# BPDC_mid.net
KiCad netlist of a schematic drawn in Altium Designer
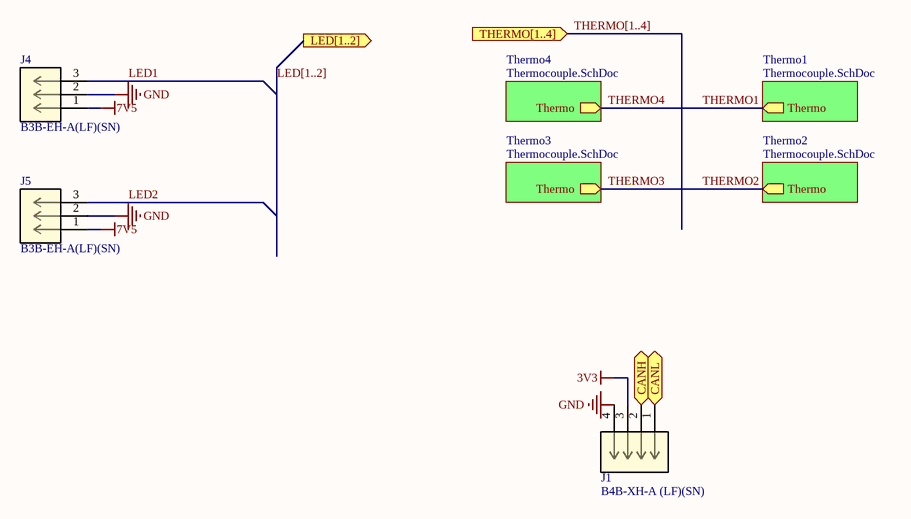
[diagram p0: BPDC mid.SchDoc]

(export (version "E")
  (design (tool "Eeschema 10.0.6"))
  (components
    (comp (ref "J1")
      (value "B4B-XH-A (LF)(SN)")
      (footprint "CONN_B4B-XH-A (LF)(SN)_JST")
      (description "No Description Available")
      (fields (field (name "COPYRIGHT") "Copyright (C) 2018 Accelerated Designs. All rights reserved"))
      (libsource (lib "BPDC conn") (part "B4B-XH-A (LF)(SN)"))
    )
    (comp (ref "J4")
      (value "B3B-EH-A(LF)(SN)")
      (footprint "CONN3_B3B-EH-A(LF)(SN)_JST")
      (description "No Description Available")
      (fields (field (name "COPYRIGHT") "Copyright (C) 2018 Accelerated Designs. All rights reserved"))
      (libsource (lib "photodiodeconn") (part "B3B-EH-A(LF)(SN)"))
    )
    (comp (ref "J5")
      (value "B3B-EH-A(LF)(SN)")
      (footprint "CONN3_B3B-EH-A(LF)(SN)_JST")
      (description "No Description Available")
      (fields (field (name "COPYRIGHT") "Copyright (C) 2018 Accelerated Designs. All rights reserved"))
      (libsource (lib "photodiodeconn") (part "B3B-EH-A(LF)(SN)"))
    )
  )
  (nets
    (net (code "1") (name "/CANH") (class "Default")
      (node (ref "J1") (pin "2") (pinfunction "2_2") (pintype "passive"))
    )
    (net (code "2") (name "/CANL") (class "Default")
      (node (ref "J1") (pin "1") (pinfunction "1_1") (pintype "passive"))
    )
    (net (code "3") (name "/LED1") (class "Default")
      (node (ref "J4") (pin "3") (pinfunction "3_3") (pintype "passive"))
    )
    (net (code "4") (name "/LED2") (class "Default")
      (node (ref "J5") (pin "3") (pinfunction "3_3") (pintype "passive"))
    )
    (net (code "9") (name "3V3") (class "Default")
      (node (ref "J1") (pin "3") (pinfunction "3_3") (pintype "passive"))
    )
    (net (code "10") (name "7V5") (class "Default")
      (node (ref "J4") (pin "1") (pinfunction "1_1") (pintype "passive"))
      (node (ref "J5") (pin "1") (pinfunction "1_1") (pintype "passive"))
    )
    (net (code "11") (name "GND") (class "Default")
      (node (ref "J1") (pin "4") (pinfunction "4_4") (pintype "passive"))
      (node (ref "J4") (pin "2") (pinfunction "2_2") (pintype "passive"))
      (node (ref "J5") (pin "2") (pinfunction "2_2") (pintype "passive"))
    )
  )
)
